# Pinto.net
KiCad netlist of a schematic drawn in Altium Designer
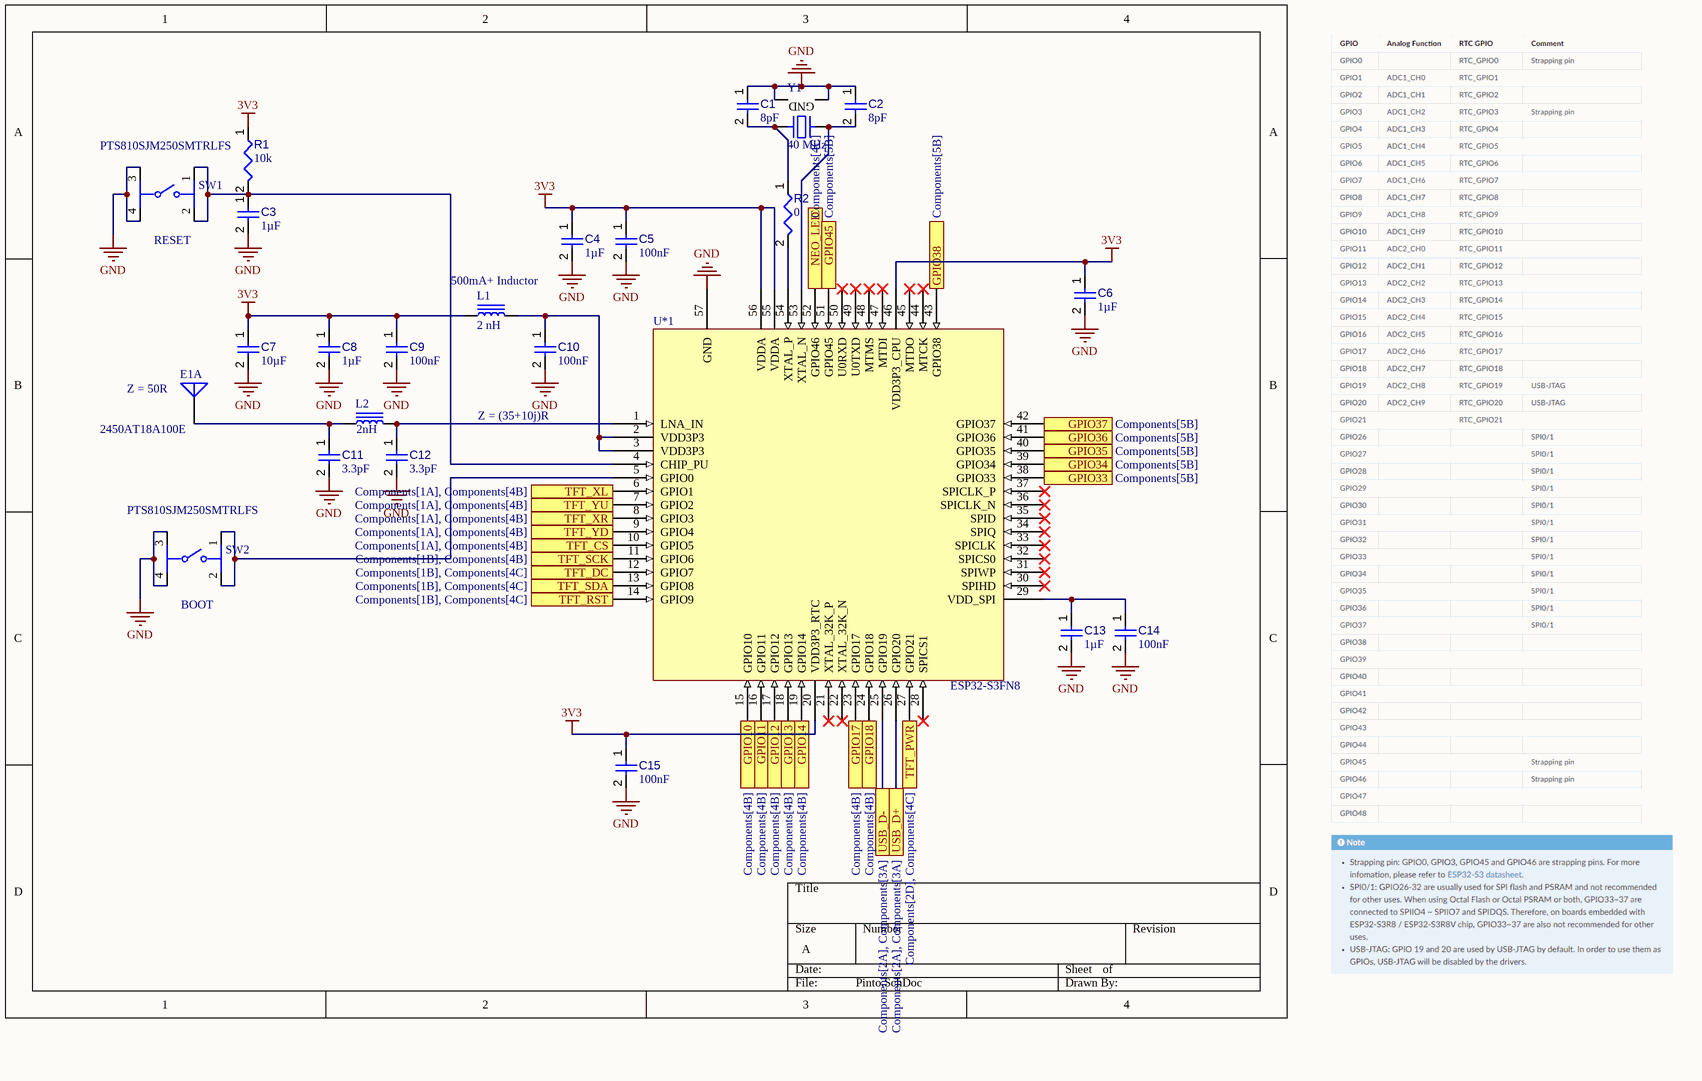
[diagram p0: Pinto.SchDoc]

(export (version "E")
  (design (tool "Eeschema 10.0.6"))
  (components
    (comp (ref "C1")
      (value "8pF")
      (footprint "CAPC0402(1005)33_L")
      (description "Chip Capacitor, 12pF +/-10%, 50V, 0402, Thickness 0.33 mm")
      (fields (field (name "TOLERANCE") "20%") (field (name "Comment") "Capacitor 12pF +/-10% 50V 0402"))
      (libsource (lib "Byron") (part "CAP-NP-2"))
    )
    (comp (ref "C2")
      (value "8pF")
      (footprint "CAPC0402(1005)33_L")
      (description "Chip Capacitor, 12pF +/-10%, 50V, 0402, Thickness 0.33 mm")
      (fields (field (name "TOLERANCE") "20%") (field (name "Comment") "Capacitor 12pF +/-10% 50V 0402"))
      (libsource (lib "Byron") (part "CAP-NP-2"))
    )
    (comp (ref "C3")
      (value "1µF")
      (footprint "CAPC0402(1005)60_L")
      (description "Chip Capacitor, 1µF +/-20%, 10V, 0402, Thickness 0.6 mm")
      (fields (field (name "TOLERANCE") "10%") (field (name "Comment") "Capacitor 1µF +/-20% 10V 0402"))
      (libsource (lib "Byron") (part "CAP-NP-2"))
    )
    (comp (ref "C4")
      (value "1µF")
      (footprint "CAPC0402(1005)60_L")
      (description "Chip Capacitor, 1µF +/-20%, 10V, 0402, Thickness 0.6 mm")
      (fields (field (name "TOLERANCE") "10%") (field (name "Comment") "Capacitor 1µF +/-20% 10V 0402"))
      (libsource (lib "Byron") (part "CAP-NP-2"))
    )
    (comp (ref "C5")
      (value "100nF")
      (footprint "CAPC0402(1005)60_L")
      (description "Chip Capacitor, 100nF +/-20%, 10V, 0402, Thickness 0.6 mm")
      (fields (field (name "TOLERANCE") "20%") (field (name "Comment") "Capacitor 100nF +/-20% 10V 0402"))
      (libsource (lib "Byron") (part "CAP-NP-2"))
    )
    (comp (ref "C6")
      (value "1µF")
      (footprint "CAPC0402(1005)60_L")
      (description "Chip Capacitor, 1µF +/-20%, 10V, 0402, Thickness 0.6 mm")
      (fields (field (name "TOLERANCE") "10%") (field (name "Comment") "Capacitor 1µF +/-20% 10V 0402"))
      (libsource (lib "Byron") (part "CAP-NP-2"))
    )
    (comp (ref "C7")
      (value "10µF")
      (footprint "CAPC0402(1005)60_L")
      (description "Chip Capacitor, 10µF +/-40%, 6.3V, 0402, Thickness 0.6 mm")
      (fields (field (name "TOLERANCE") "10%") (field (name "Comment") "Capacitor 10µF +/-40% 6.3V 0402"))
      (libsource (lib "Byron") (part "CAP-NP-2"))
    )
    (comp (ref "C8")
      (value "1µF")
      (footprint "CAPC0402(1005)60_L")
      (description "Chip Capacitor, 1µF +/-20%, 10V, 0402, Thickness 0.6 mm")
      (fields (field (name "TOLERANCE") "10%") (field (name "Comment") "Capacitor 1µF +/-20% 10V 0402"))
      (libsource (lib "Byron") (part "CAP-NP-2"))
    )
    (comp (ref "C9")
      (value "100nF")
      (footprint "CAPC0402(1005)60_L")
      (description "Chip Capacitor, 100nF +/-20%, 10V, 0402, Thickness 0.6 mm")
      (fields (field (name "TOLERANCE") "20%") (field (name "Comment") "Capacitor 100nF +/-20% 10V 0402"))
      (libsource (lib "Byron") (part "CAP-NP-2"))
    )
    (comp (ref "C10")
      (value "100nF")
      (footprint "CAPC0402(1005)60_L")
      (description "Chip Capacitor, 100nF +/-20%, 10V, 0402, Thickness 0.6 mm")
      (fields (field (name "TOLERANCE") "20%") (field (name "Comment") "Capacitor 100nF +/-20% 10V 0402"))
      (libsource (lib "Byron") (part "CAP-NP-2"))
    )
    (comp (ref "C11")
      (value "3.3pF")
      (footprint "CAPC1005X56X25LL10T15")
      (description "Chip Capacitor, 0.1 uF, +/- 5%, 16 V, 0402 (1005 Metric)")
      (fields (field (name "TOLERANCE") "5%") (field (name "Comment") "Capacitor 0.1 uF +/- 5% 16 V 0402"))
      (libsource (lib "Byron") (part "CAP-NP-2"))
    )
    (comp (ref "C12")
      (value "3.3pF")
      (footprint "CAPC1005X56X25LL10T15")
      (description "Chip Capacitor, 0.1 uF, +/- 5%, 16 V, 0402 (1005 Metric)")
      (fields (field (name "TOLERANCE") "5%") (field (name "Comment") "Capacitor 0.1 uF +/- 5% 16 V 0402"))
      (libsource (lib "Byron") (part "CAP-NP-2"))
    )
    (comp (ref "C13")
      (value "1µF")
      (footprint "CAPC0402(1005)60_L")
      (description "Chip Capacitor, 1µF +/-20%, 10V, 0402, Thickness 0.6 mm")
      (fields (field (name "TOLERANCE") "10%") (field (name "Comment") "Capacitor 1µF +/-20% 10V 0402"))
      (libsource (lib "Byron") (part "CAP-NP-2"))
    )
    (comp (ref "C14")
      (value "100nF")
      (footprint "CAPC0402(1005)60_L")
      (description "Chip Capacitor, 100nF +/-20%, 10V, 0402, Thickness 0.6 mm")
      (fields (field (name "TOLERANCE") "20%") (field (name "Comment") "Capacitor 100nF +/-20% 10V 0402"))
      (libsource (lib "Byron") (part "CAP-NP-2"))
    )
    (comp (ref "C15")
      (value "100nF")
      (footprint "CAPC0402(1005)60_L")
      (description "Chip Capacitor, 100nF +/-20%, 10V, 0402, Thickness 0.6 mm")
      (fields (field (name "TOLERANCE") "20%") (field (name "Comment") "Capacitor 100nF +/-20% 10V 0402"))
      (libsource (lib "Byron") (part "CAP-NP-2"))
    )
    (comp (ref "E1")
      (value "2450AT18A100E")
      (footprint "JT-2450AT18A100-2_V")
      (description "Ceramic Antenna, 2.45 GHZ, 2 W, -40 to 125 degC, 2-Pin SMD, RoHS, Tape and Reel")
      (fields (field (name "MANUFACTURER") "Johanson Technology"))
      (libsource (lib "Altium Content Vault") (part "JT-2450AT18A100-2"))
    )
    (comp (ref "L1")
      (value "2 nH")
      (footprint "IND 0201_0603")
      (description "INDUCTOR FIXED 2.0NH 0201")
      (fields
        (field (name "PART NUMBER") "WLCM0603TGB2N0TB")
        (field (name "MANUFACTURER") "Walsin Technology Corporation")
      )
      (libsource (lib "Celestial Altium Library - altium_library") (part "Inductor"))
    )
    (comp (ref "L2")
      (value "2nH")
      (footprint "IND 0201_0603")
      (description "INDUCTOR FIXED 2.0NH 0201")
      (fields
        (field (name "PART NUMBER") "WLCM0603TGB2N0TB")
        (field (name "MANUFACTURER") "Walsin Technology Corporation")
      )
      (libsource (lib "Celestial Altium Library - altium_library") (part "Inductor"))
    )
    (comp (ref "R1")
      (value "10k")
      (footprint "RESC0402(1005)_L")
      (description "10K 0.063W 1% 0402 (1005 Metric)  SMD")
      (fields (field (name "POWER") "63mW") (field (name "TOLERANCE") "1%"))
      (libsource (lib "Byron") (part "10KR2F"))
    )
    (comp (ref "R2")
      (value "0")
      (footprint "RESC0402(1005)_L")
      (description "Jumper 0402 (1005 Metric)")
      (fields (field (name "Comment") "0R2J"))
      (libsource (lib "Byron") (part "0R2J"))
    )
    (comp (ref "SW1")
      (value "PTS810SJM250SMTRLFS")
      (footprint "FP-PTS810SJM250SMTRLFS-MFG")
      (description "SWITCH TACTILE SPST-NO 0.05A 16V")
      (libsource (lib "Altium Content Vault") (part "1adf0dd01260c80cf25a44bfd6b99ba"))
    )
    (comp (ref "SW2")
      (value "PTS810SJM250SMTRLFS")
      (footprint "FP-PTS810SJM250SMTRLFS-MFG")
      (description "SWITCH TACTILE SPST-NO 0.05A 16V")
      (libsource (lib "Altium Content Vault") (part "1adf0dd01260c80cf25a44bfd6b99ba"))
    )
    (comp (ref "U*1")
      (value "ESP32-S3FN8")
      (footprint "PCBComponent_1")
      (description "ESP32 MCU")
      (libsource (lib "ESP32-S3FN8") (part "ESP32-S3FN8"))
    )
    (comp (ref "Y1")
      (value "40 MHz")
      (footprint "NDK NX3225SA")
      (description "CRYSTAL 40.0000MHZ 10PF SMD")
      (fields
        (field (name "PART NUMBER") "NX3225SA-40M-EXS00A-CS03880")
        (field (name "MANUFACTURER") "NDK America, Inc.")
      )
      (libsource (lib "Celestial Altium Library - altium_library") (part "NDK Crystal NX3225SA"))
    )
  )
  (nets
    (net (code "1") (name "/GPIO10") (class "Default")
      (node (ref "U*1") (pin "15") (pinfunction "GPIO10_15") (pintype "input"))
    )
    (net (code "2") (name "/GPIO11") (class "Default")
      (node (ref "U*1") (pin "16") (pinfunction "GPIO11_16") (pintype "input"))
    )
    (net (code "3") (name "/GPIO12") (class "Default")
      (node (ref "U*1") (pin "17") (pinfunction "GPIO12_17") (pintype "input"))
    )
    (net (code "4") (name "/GPIO13") (class "Default")
      (node (ref "U*1") (pin "18") (pinfunction "GPIO13_18") (pintype "input"))
    )
    (net (code "5") (name "/GPIO14") (class "Default")
      (node (ref "U*1") (pin "19") (pinfunction "GPIO14_19") (pintype "input"))
    )
    (net (code "6") (name "/GPIO17") (class "Default")
      (node (ref "U*1") (pin "23") (pinfunction "GPIO17_23") (pintype "input"))
    )
    (net (code "7") (name "/GPIO18") (class "Default")
      (node (ref "U*1") (pin "24") (pinfunction "GPIO18_24") (pintype "input"))
    )
    (net (code "8") (name "/GPIO33") (class "Default")
      (node (ref "U*1") (pin "38") (pinfunction "GPIO33_38") (pintype "input"))
    )
    (net (code "9") (name "/GPIO34") (class "Default")
      (node (ref "U*1") (pin "39") (pinfunction "GPIO34_39") (pintype "input"))
    )
    (net (code "10") (name "/GPIO35") (class "Default")
      (node (ref "U*1") (pin "40") (pinfunction "GPIO35_40") (pintype "input"))
    )
    (net (code "11") (name "/GPIO36") (class "Default")
      (node (ref "U*1") (pin "41") (pinfunction "GPIO36_41") (pintype "input"))
    )
    (net (code "12") (name "/GPIO37") (class "Default")
      (node (ref "U*1") (pin "42") (pinfunction "GPIO37_42") (pintype "input"))
    )
    (net (code "13") (name "/GPIO38") (class "Default")
      (node (ref "U*1") (pin "43") (pinfunction "GPIO38_43") (pintype "input"))
    )
    (net (code "14") (name "/GPIO45") (class "Default")
      (node (ref "U*1") (pin "51") (pinfunction "GPIO45_51") (pintype "input"))
    )
    (net (code "15") (name "/NEO_LED") (class "Default")
      (node (ref "U*1") (pin "52") (pinfunction "GPIO46_52") (pintype "input"))
    )
    (net (code "16") (name "/TFT_CS") (class "Default")
      (node (ref "U*1") (pin "10") (pinfunction "GPIO5_10") (pintype "input"))
    )
    (net (code "17") (name "/TFT_DC") (class "Default")
      (node (ref "U*1") (pin "12") (pinfunction "GPIO7_12") (pintype "input"))
    )
    (net (code "18") (name "/TFT_PWR") (class "Default")
      (node (ref "U*1") (pin "27") (pinfunction "GPIO21_27") (pintype "input"))
    )
    (net (code "19") (name "/TFT_RST") (class "Default")
      (node (ref "U*1") (pin "14") (pinfunction "GPIO9_14") (pintype "input"))
    )
    (net (code "20") (name "/TFT_SCK") (class "Default")
      (node (ref "U*1") (pin "11") (pinfunction "GPIO6_11") (pintype "input"))
    )
    (net (code "21") (name "/TFT_SDA") (class "Default")
      (node (ref "U*1") (pin "13") (pinfunction "GPIO8_13") (pintype "input"))
    )
    (net (code "22") (name "/TFT_XL") (class "Default")
      (node (ref "U*1") (pin "6") (pinfunction "GPIO1_6") (pintype "input"))
    )
    (net (code "23") (name "/TFT_XR") (class "Default")
      (node (ref "U*1") (pin "8") (pinfunction "GPIO3_8") (pintype "input"))
    )
    (net (code "24") (name "/TFT_YD") (class "Default")
      (node (ref "U*1") (pin "9") (pinfunction "GPIO4_9") (pintype "input"))
    )
    (net (code "25") (name "/TFT_YU") (class "Default")
      (node (ref "U*1") (pin "7") (pinfunction "GPIO2_7") (pintype "input"))
    )
    (net (code "26") (name "/USB_D+") (class "Default")
      (node (ref "U*1") (pin "26") (pinfunction "GPIO20_26") (pintype "input"))
    )
    (net (code "27") (name "/USB_D-") (class "Default")
      (node (ref "U*1") (pin "25") (pinfunction "GPIO19_25") (pintype "input"))
    )
    (net (code "28") (name "3V3") (class "Default")
      (node (ref "C15") (pin "1") (pinfunction "1_1") (pintype "passive"))
      (node (ref "C4") (pin "1") (pinfunction "1_1") (pintype "passive"))
      (node (ref "C5") (pin "1") (pinfunction "1_1") (pintype "passive"))
      (node (ref "C6") (pin "1") (pinfunction "1_1") (pintype "passive"))
      (node (ref "C7") (pin "1") (pinfunction "1_1") (pintype "passive"))
      (node (ref "C8") (pin "1") (pinfunction "1_1") (pintype "passive"))
      (node (ref "C9") (pin "1") (pinfunction "1_1") (pintype "passive"))
      (node (ref "L1") (pin "1") (pinfunction "1_1") (pintype "passive"))
      (node (ref "R1") (pin "1") (pinfunction "1_1") (pintype "passive"))
      (node (ref "U*1") (pin "20") (pinfunction "VDD3P3_RTC_20") (pintype "power_in"))
      (node (ref "U*1") (pin "46") (pinfunction "VDD3P3_CPU_46") (pintype "power_in"))
      (node (ref "U*1") (pin "55") (pinfunction "VDDA_55") (pintype "power_in"))
      (node (ref "U*1") (pin "56") (pinfunction "VDDA_56") (pintype "power_in"))
    )
    (net (code "29") (name "GND") (class "Default")
      (node (ref "C1") (pin "1") (pinfunction "1_1") (pintype "passive"))
      (node (ref "C10") (pin "2") (pinfunction "2_2") (pintype "passive"))
      (node (ref "C11") (pin "2") (pinfunction "2_2") (pintype "passive"))
      (node (ref "C12") (pin "2") (pinfunction "2_2") (pintype "passive"))
      (node (ref "C13") (pin "2") (pinfunction "2_2") (pintype "passive"))
      (node (ref "C14") (pin "2") (pinfunction "2_2") (pintype "passive"))
      (node (ref "C15") (pin "2") (pinfunction "2_2") (pintype "passive"))
      (node (ref "C2") (pin "1") (pinfunction "1_1") (pintype "passive"))
      (node (ref "C3") (pin "2") (pinfunction "2_2") (pintype "passive"))
      (node (ref "C4") (pin "2") (pinfunction "2_2") (pintype "passive"))
      (node (ref "C5") (pin "2") (pinfunction "2_2") (pintype "passive"))
      (node (ref "C6") (pin "2") (pinfunction "2_2") (pintype "passive"))
      (node (ref "C7") (pin "2") (pinfunction "2_2") (pintype "passive"))
      (node (ref "C8") (pin "2") (pinfunction "2_2") (pintype "passive"))
      (node (ref "C9") (pin "2") (pinfunction "2_2") (pintype "passive"))
      (node (ref "SW1") (pin "3") (pinfunction "3_3") (pintype "passive"))
      (node (ref "SW1") (pin "4") (pinfunction "4_4") (pintype "passive"))
      (node (ref "SW2") (pin "3") (pinfunction "3_3") (pintype "passive"))
      (node (ref "SW2") (pin "4") (pinfunction "4_4") (pintype "passive"))
      (node (ref "U*1") (pin "57") (pinfunction "GND_57") (pintype "power_in"))
      (node (ref "Y1") (pin "2") (pinfunction "GND_2") (pintype "passive"))
      (node (ref "Y1") (pin "4") (pinfunction "GND_4") (pintype "passive"))
    )
    (net (code "30") (name "Net-(C1-Pad2)") (class "Default")
      (node (ref "C1") (pin "2") (pinfunction "2_2") (pintype "passive"))
      (node (ref "R2") (pin "1") (pinfunction "1_1") (pintype "passive"))
      (node (ref "Y1") (pin "3") (pinfunction "3_3") (pintype "passive"))
    )
    (net (code "31") (name "Net-(C10-Pad1)") (class "Default")
      (node (ref "C10") (pin "1") (pinfunction "1_1") (pintype "passive"))
      (node (ref "L1") (pin "2") (pinfunction "2_2") (pintype "passive"))
      (node (ref "U*1") (pin "2") (pinfunction "VDD3P3_2") (pintype "power_in"))
      (node (ref "U*1") (pin "3") (pinfunction "VDD3P3_3") (pintype "power_in"))
    )
    (net (code "32") (name "Net-(E1A-FP)") (class "Default")
      (node (ref "C11") (pin "1") (pinfunction "1_1") (pintype "passive"))
      (node (ref "E1") (pin "1") (pinfunction "FP_1") (pintype "passive"))
      (node (ref "L2") (pin "1") (pinfunction "1_1") (pintype "passive"))
    )
    (net (code "33") (name "Net-(U*1-CHIP_PU)") (class "Default")
      (node (ref "C3") (pin "1") (pinfunction "1_1") (pintype "passive"))
      (node (ref "R1") (pin "2") (pinfunction "2_2") (pintype "passive"))
      (node (ref "SW1") (pin "1") (pinfunction "1_1") (pintype "passive"))
      (node (ref "SW1") (pin "2") (pinfunction "2_2") (pintype "passive"))
      (node (ref "U*1") (pin "4") (pinfunction "CHIP_PU_4") (pintype "input"))
    )
    (net (code "34") (name "Net-(U*1-GPIO0)") (class "Default")
      (node (ref "SW2") (pin "1") (pinfunction "1_1") (pintype "passive"))
      (node (ref "SW2") (pin "2") (pinfunction "2_2") (pintype "passive"))
      (node (ref "U*1") (pin "5") (pinfunction "GPIO0_5") (pintype "input"))
    )
    (net (code "35") (name "Net-(U*1-LNA_IN)") (class "Default")
      (node (ref "C12") (pin "1") (pinfunction "1_1") (pintype "passive"))
      (node (ref "L2") (pin "2") (pinfunction "2_2") (pintype "passive"))
      (node (ref "U*1") (pin "1") (pinfunction "LNA_IN_1") (pintype "input"))
    )
    (net (code "36") (name "Net-(U*1-VDD_SPI)") (class "Default")
      (node (ref "C13") (pin "1") (pinfunction "1_1") (pintype "passive"))
      (node (ref "C14") (pin "1") (pinfunction "1_1") (pintype "passive"))
      (node (ref "U*1") (pin "29") (pinfunction "VDD_SPI_29") (pintype "power_in"))
    )
    (net (code "37") (name "Net-(U*1-XTAL_N)") (class "Default")
      (node (ref "C2") (pin "2") (pinfunction "2_2") (pintype "passive"))
      (node (ref "U*1") (pin "53") (pinfunction "XTAL_N_53") (pintype "input"))
      (node (ref "Y1") (pin "1") (pinfunction "1_1") (pintype "passive"))
    )
    (net (code "38") (name "Net-(U*1-XTAL_P)") (class "Default")
      (node (ref "R2") (pin "2") (pinfunction "2_2") (pintype "passive"))
      (node (ref "U*1") (pin "54") (pinfunction "XTAL_P_54") (pintype "input"))
    )
    (net (code "39") (name "unconnected-(U*1-MTCK-Pad44)") (class "Default")
      (node (ref "U*1") (pin "44") (pinfunction "MTCK_44") (pintype "input+no_connect"))
    )
    (net (code "40") (name "unconnected-(U*1-MTDI-Pad47)") (class "Default")
      (node (ref "U*1") (pin "47") (pinfunction "MTDI_47") (pintype "input+no_connect"))
    )
    (net (code "41") (name "unconnected-(U*1-MTDO-Pad45)") (class "Default")
      (node (ref "U*1") (pin "45") (pinfunction "MTDO_45") (pintype "input+no_connect"))
    )
    (net (code "42") (name "unconnected-(U*1-MTMS-Pad48)") (class "Default")
      (node (ref "U*1") (pin "48") (pinfunction "MTMS_48") (pintype "input+no_connect"))
    )
    (net (code "43") (name "unconnected-(U*1-SPICLK-Pad33)") (class "Default")
      (node (ref "U*1") (pin "33") (pinfunction "SPICLK_33") (pintype "input+no_connect"))
    )
    (net (code "44") (name "unconnected-(U*1-SPICLK_N-Pad36)") (class "Default")
      (node (ref "U*1") (pin "36") (pinfunction "SPICLK_N_36") (pintype "input+no_connect"))
    )
    (net (code "45") (name "unconnected-(U*1-SPICLK_P-Pad37)") (class "Default")
      (node (ref "U*1") (pin "37") (pinfunction "SPICLK_P_37") (pintype "input+no_connect"))
    )
    (net (code "46") (name "unconnected-(U*1-SPICS0-Pad32)") (class "Default")
      (node (ref "U*1") (pin "32") (pinfunction "SPICS0_32") (pintype "input+no_connect"))
    )
    (net (code "47") (name "unconnected-(U*1-SPICS1-Pad28)") (class "Default")
      (node (ref "U*1") (pin "28") (pinfunction "SPICS1_28") (pintype "input+no_connect"))
    )
    (net (code "48") (name "unconnected-(U*1-SPID-Pad35)") (class "Default")
      (node (ref "U*1") (pin "35") (pinfunction "SPID_35") (pintype "input+no_connect"))
    )
    (net (code "49") (name "unconnected-(U*1-SPIHD-Pad30)") (class "Default")
      (node (ref "U*1") (pin "30") (pinfunction "SPIHD_30") (pintype "input+no_connect"))
    )
    (net (code "50") (name "unconnected-(U*1-SPIQ-Pad34)") (class "Default")
      (node (ref "U*1") (pin "34") (pinfunction "SPIQ_34") (pintype "input+no_connect"))
    )
    (net (code "51") (name "unconnected-(U*1-SPIWP-Pad31)") (class "Default")
      (node (ref "U*1") (pin "31") (pinfunction "SPIWP_31") (pintype "input+no_connect"))
    )
    (net (code "52") (name "unconnected-(U*1-U0RXD-Pad50)") (class "Default")
      (node (ref "U*1") (pin "50") (pinfunction "U0RXD_50") (pintype "input+no_connect"))
    )
    (net (code "53") (name "unconnected-(U*1-U0TXD-Pad49)") (class "Default")
      (node (ref "U*1") (pin "49") (pinfunction "U0TXD_49") (pintype "input+no_connect"))
    )
    (net (code "54") (name "unconnected-(U*1-XTAL_32K_N-Pad22)") (class "Default")
      (node (ref "U*1") (pin "22") (pinfunction "XTAL_32K_N_22") (pintype "input+no_connect"))
    )
    (net (code "55") (name "unconnected-(U*1-XTAL_32K_P-Pad21)") (class "Default")
      (node (ref "U*1") (pin "21") (pinfunction "XTAL_32K_P_21") (pintype "input+no_connect"))
    )
  )
)
